# Main_Board_CAN_Modules.net
KiCad netlist of a schematic drawn in Altium Designer
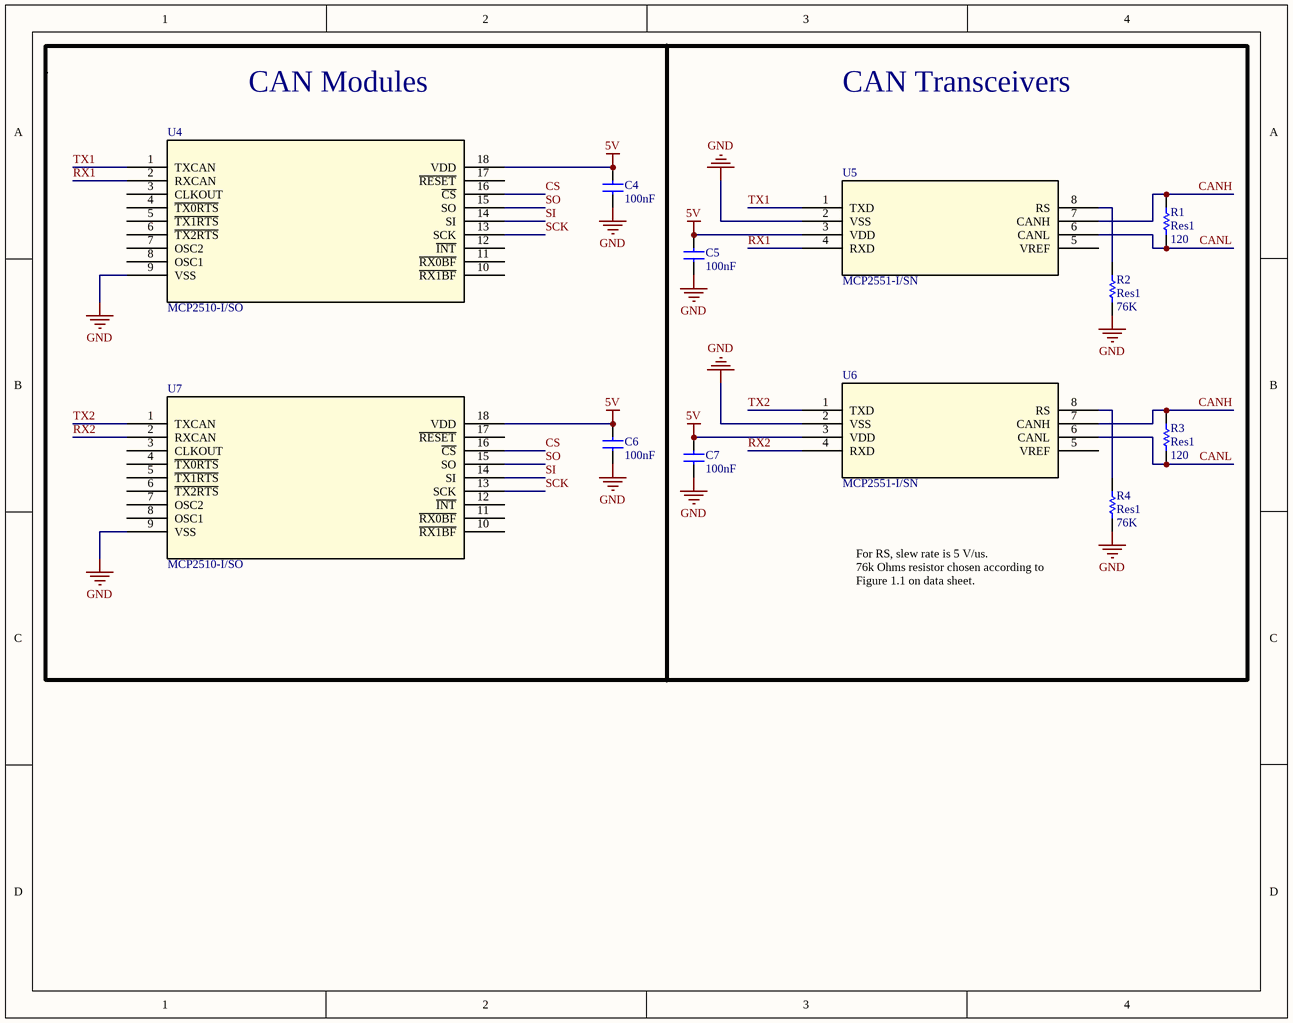
[diagram p0: Main Board CAN Modules.SchDoc]

(export (version "E")
  (design (tool "Eeschema 10.0.6"))
  (components
    (comp (ref "C4")
      (value "100nF")
      (footprint "CAPC0603")
      (fields (field (name "Comment") "Cap"))
      (libsource (lib "Passives") (part "Cap"))
    )
    (comp (ref "C5")
      (value "100nF")
      (footprint "CAPC0603")
      (fields (field (name "Comment") "Cap"))
      (libsource (lib "Passives") (part "Cap"))
    )
    (comp (ref "C6")
      (value "100nF")
      (footprint "CAPC0603")
      (fields (field (name "Comment") "Cap"))
      (libsource (lib "Passives") (part "Cap"))
    )
    (comp (ref "C7")
      (value "100nF")
      (footprint "CAPC0603")
      (fields (field (name "Comment") "Cap"))
      (libsource (lib "Passives") (part "Cap"))
    )
    (comp (ref "R1")
      (value "Res1")
      (footprint "AXIAL-0.3")
      (description "Resistor")
      (fields (field (name "ALTIUM_VALUE") "120") (field (name "PUBLISHER") "Altium Limited"))
      (libsource (lib "Miscellaneous Devices") (part "Res1"))
    )
    (comp (ref "R2")
      (value "Res1")
      (footprint "AXIAL-0.3")
      (description "Resistor")
      (fields (field (name "ALTIUM_VALUE") "76K") (field (name "PUBLISHER") "Altium Limited"))
      (libsource (lib "Miscellaneous Devices") (part "Res1"))
    )
    (comp (ref "R3")
      (value "Res1")
      (footprint "AXIAL-0.3")
      (description "Resistor")
      (fields (field (name "ALTIUM_VALUE") "120") (field (name "PUBLISHER") "Altium Limited"))
      (libsource (lib "Miscellaneous Devices") (part "Res1"))
    )
    (comp (ref "R4")
      (value "Res1")
      (footprint "AXIAL-0.3")
      (description "Resistor")
      (fields (field (name "ALTIUM_VALUE") "76K") (field (name "PUBLISHER") "Altium Limited"))
      (libsource (lib "Miscellaneous Devices") (part "Res1"))
    )
    (comp (ref "U4")
      (value "MCP2510-I/SO")
      (footprint "SOIC18-W_MC_MCH")
      (description "No Description Available")
      (libsource (lib "ICs") (part "MCP2510-I/SO"))
    )
    (comp (ref "U5")
      (value "MCP2551-I/SN")
      (footprint "SOIC8-N_MC_MCH")
      (description "No Description Available")
      (libsource (lib "ICs") (part "MCP2551-I/SN"))
    )
    (comp (ref "U6")
      (value "MCP2551-I/SN")
      (footprint "SOIC8-N_MC_MCH")
      (description "No Description Available")
      (libsource (lib "ICs") (part "MCP2551-I/SN"))
    )
    (comp (ref "U7")
      (value "MCP2510-I/SO")
      (footprint "SOIC18-W_MC_MCH")
      (description "No Description Available")
      (libsource (lib "ICs") (part "MCP2510-I/SO"))
    )
  )
  (nets
    (net (code "1") (name "/CANH") (class "Default")
      (node (ref "R1") (pin "2") (pinfunction "2_2") (pintype "passive"))
      (node (ref "R3") (pin "2") (pinfunction "2_2") (pintype "passive"))
      (node (ref "U5") (pin "7") (pinfunction "CANH_7") (pintype "passive"))
      (node (ref "U6") (pin "7") (pinfunction "CANH_7") (pintype "passive"))
    )
    (net (code "2") (name "/CANL") (class "Default")
      (node (ref "R1") (pin "1") (pinfunction "1_1") (pintype "passive"))
      (node (ref "R3") (pin "1") (pinfunction "1_1") (pintype "passive"))
      (node (ref "U5") (pin "6") (pinfunction "CANL_6") (pintype "passive"))
      (node (ref "U6") (pin "6") (pinfunction "CANL_6") (pintype "passive"))
    )
    (net (code "3") (name "/CS") (class "Default")
      (node (ref "U4") (pin "16") (pinfunction "CS_16") (pintype "passive"))
      (node (ref "U7") (pin "16") (pinfunction "CS_16") (pintype "passive"))
    )
    (net (code "4") (name "/RX1") (class "Default")
      (node (ref "U4") (pin "2") (pinfunction "RXCAN_2") (pintype "passive"))
      (node (ref "U5") (pin "4") (pinfunction "RXD_4") (pintype "passive"))
    )
    (net (code "5") (name "/RX2") (class "Default")
      (node (ref "U6") (pin "4") (pinfunction "RXD_4") (pintype "passive"))
      (node (ref "U7") (pin "2") (pinfunction "RXCAN_2") (pintype "passive"))
    )
    (net (code "6") (name "/SCK") (class "Default")
      (node (ref "U4") (pin "13") (pinfunction "SCK_13") (pintype "passive"))
      (node (ref "U7") (pin "13") (pinfunction "SCK_13") (pintype "passive"))
    )
    (net (code "7") (name "/SI") (class "Default")
      (node (ref "U4") (pin "14") (pinfunction "SI_14") (pintype "passive"))
      (node (ref "U7") (pin "14") (pinfunction "SI_14") (pintype "passive"))
    )
    (net (code "8") (name "/SO") (class "Default")
      (node (ref "U4") (pin "15") (pinfunction "SO_15") (pintype "passive"))
      (node (ref "U7") (pin "15") (pinfunction "SO_15") (pintype "passive"))
    )
    (net (code "9") (name "/TX1") (class "Default")
      (node (ref "U4") (pin "1") (pinfunction "TXCAN_1") (pintype "passive"))
      (node (ref "U5") (pin "1") (pinfunction "TXD_1") (pintype "passive"))
    )
    (net (code "10") (name "/TX2") (class "Default")
      (node (ref "U6") (pin "1") (pinfunction "TXD_1") (pintype "passive"))
      (node (ref "U7") (pin "1") (pinfunction "TXCAN_1") (pintype "passive"))
    )
    (net (code "11") (name "5V") (class "Default")
      (node (ref "C4") (pin "1") (pinfunction "A_1") (pintype "passive"))
      (node (ref "C5") (pin "1") (pinfunction "A_1") (pintype "passive"))
      (node (ref "C6") (pin "1") (pinfunction "A_1") (pintype "passive"))
      (node (ref "C7") (pin "1") (pinfunction "A_1") (pintype "passive"))
      (node (ref "U4") (pin "18") (pinfunction "VDD_18") (pintype "passive"))
      (node (ref "U5") (pin "3") (pinfunction "VDD_3") (pintype "passive"))
      (node (ref "U6") (pin "3") (pinfunction "VDD_3") (pintype "passive"))
      (node (ref "U7") (pin "18") (pinfunction "VDD_18") (pintype "passive"))
    )
    (net (code "12") (name "GND") (class "Default")
      (node (ref "C4") (pin "2") (pinfunction "B_2") (pintype "passive"))
      (node (ref "C5") (pin "2") (pinfunction "B_2") (pintype "passive"))
      (node (ref "C6") (pin "2") (pinfunction "B_2") (pintype "passive"))
      (node (ref "C7") (pin "2") (pinfunction "B_2") (pintype "passive"))
      (node (ref "R2") (pin "2") (pinfunction "2_2") (pintype "passive"))
      (node (ref "R4") (pin "2") (pinfunction "2_2") (pintype "passive"))
      (node (ref "U4") (pin "9") (pinfunction "VSS_9") (pintype "passive"))
      (node (ref "U5") (pin "2") (pinfunction "VSS_2") (pintype "passive"))
      (node (ref "U6") (pin "2") (pinfunction "VSS_2") (pintype "passive"))
      (node (ref "U7") (pin "9") (pinfunction "VSS_9") (pintype "passive"))
    )
    (net (code "13") (name "Net-(U5-RS)") (class "Default")
      (node (ref "R2") (pin "1") (pinfunction "1_1") (pintype "passive"))
      (node (ref "U5") (pin "8") (pinfunction "RS_8") (pintype "passive"))
    )
    (net (code "14") (name "Net-(U6-RS)") (class "Default")
      (node (ref "R4") (pin "1") (pinfunction "1_1") (pintype "passive"))
      (node (ref "U6") (pin "8") (pinfunction "RS_8") (pintype "passive"))
    )
    (net (code "15") (name "unconnected-(U4-CLKOUT-Pad3)") (class "Default")
      (node (ref "U4") (pin "3") (pinfunction "CLKOUT_3") (pintype "passive"))
    )
    (net (code "16") (name "unconnected-(U4-INT-Pad12)") (class "Default")
      (node (ref "U4") (pin "12") (pinfunction "INT_12") (pintype "passive"))
    )
    (net (code "17") (name "unconnected-(U4-OSC1-Pad8)") (class "Default")
      (node (ref "U4") (pin "8") (pinfunction "OSC1_8") (pintype "passive"))
    )
    (net (code "18") (name "unconnected-(U4-OSC2-Pad7)") (class "Default")
      (node (ref "U4") (pin "7") (pinfunction "OSC2_7") (pintype "passive"))
    )
    (net (code "19") (name "unconnected-(U4-RESET-Pad17)") (class "Default")
      (node (ref "U4") (pin "17") (pinfunction "RESET_17") (pintype "passive"))
    )
    (net (code "20") (name "unconnected-(U4-RX0BF-Pad11)") (class "Default")
      (node (ref "U4") (pin "11") (pinfunction "RX0BF_11") (pintype "passive"))
    )
    (net (code "21") (name "unconnected-(U4-RX1BF-Pad10)") (class "Default")
      (node (ref "U4") (pin "10") (pinfunction "RX1BF_10") (pintype "passive"))
    )
    (net (code "22") (name "unconnected-(U4-TX0RTS-Pad4)") (class "Default")
      (node (ref "U4") (pin "4") (pinfunction "TX0RTS_4") (pintype "passive"))
    )
    (net (code "23") (name "unconnected-(U4-TX1RTS-Pad5)") (class "Default")
      (node (ref "U4") (pin "5") (pinfunction "TX1RTS_5") (pintype "passive"))
    )
    (net (code "24") (name "unconnected-(U4-TX2RTS-Pad6)") (class "Default")
      (node (ref "U4") (pin "6") (pinfunction "TX2RTS_6") (pintype "passive"))
    )
    (net (code "25") (name "unconnected-(U5-VREF-Pad5)") (class "Default")
      (node (ref "U5") (pin "5") (pinfunction "VREF_5") (pintype "passive"))
    )
    (net (code "26") (name "unconnected-(U6-VREF-Pad5)") (class "Default")
      (node (ref "U6") (pin "5") (pinfunction "VREF_5") (pintype "passive"))
    )
    (net (code "27") (name "unconnected-(U7-CLKOUT-Pad3)") (class "Default")
      (node (ref "U7") (pin "3") (pinfunction "CLKOUT_3") (pintype "passive"))
    )
    (net (code "28") (name "unconnected-(U7-INT-Pad12)") (class "Default")
      (node (ref "U7") (pin "12") (pinfunction "INT_12") (pintype "passive"))
    )
    (net (code "29") (name "unconnected-(U7-OSC1-Pad8)") (class "Default")
      (node (ref "U7") (pin "8") (pinfunction "OSC1_8") (pintype "passive"))
    )
    (net (code "30") (name "unconnected-(U7-OSC2-Pad7)") (class "Default")
      (node (ref "U7") (pin "7") (pinfunction "OSC2_7") (pintype "passive"))
    )
    (net (code "31") (name "unconnected-(U7-RESET-Pad17)") (class "Default")
      (node (ref "U7") (pin "17") (pinfunction "RESET_17") (pintype "passive"))
    )
    (net (code "32") (name "unconnected-(U7-RX0BF-Pad11)") (class "Default")
      (node (ref "U7") (pin "11") (pinfunction "RX0BF_11") (pintype "passive"))
    )
    (net (code "33") (name "unconnected-(U7-RX1BF-Pad10)") (class "Default")
      (node (ref "U7") (pin "10") (pinfunction "RX1BF_10") (pintype "passive"))
    )
    (net (code "34") (name "unconnected-(U7-TX0RTS-Pad4)") (class "Default")
      (node (ref "U7") (pin "4") (pinfunction "TX0RTS_4") (pintype "passive"))
    )
    (net (code "35") (name "unconnected-(U7-TX1RTS-Pad5)") (class "Default")
      (node (ref "U7") (pin "5") (pinfunction "TX1RTS_5") (pintype "passive"))
    )
    (net (code "36") (name "unconnected-(U7-TX2RTS-Pad6)") (class "Default")
      (node (ref "U7") (pin "6") (pinfunction "TX2RTS_6") (pintype "passive"))
    )
  )
)
